# sch1.net
KiCad netlist of a schematic drawn in EAGLE
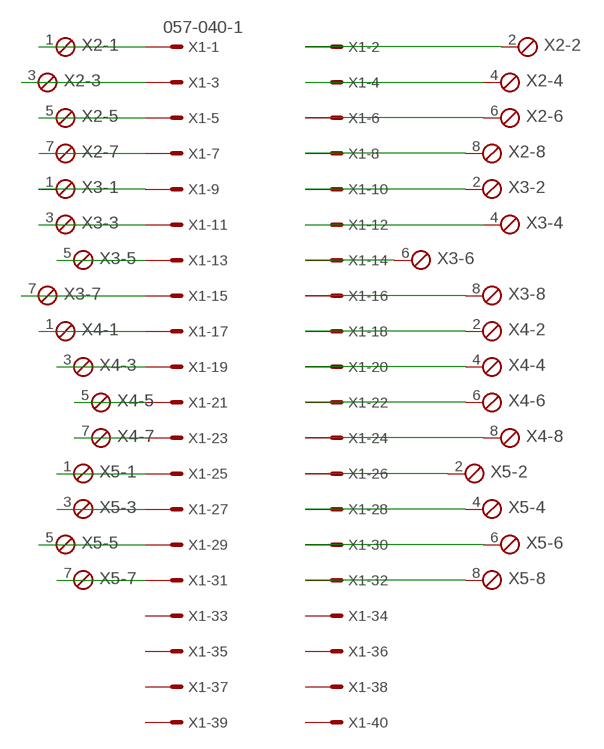
[diagram p0: schematic, sheet 1]

(export (version "E")
  (design (tool "Eeschema 10.0.6"))
  (components
    (comp (ref "X1")
      (value "057-040-1")
      (footprint "eagle-import:057-040-1")
      (libsource (lib "eagle-import") (part "057-040-1"))
    )
    (comp (ref "X2")
      (value "MPT8")
      (footprint "eagle-import:8POL254")
      (libsource (lib "eagle-import") (part "MPT8"))
    )
    (comp (ref "X3")
      (value "MPT8")
      (footprint "eagle-import:8POL254")
      (libsource (lib "eagle-import") (part "MPT8"))
    )
    (comp (ref "X4")
      (value "MPT8")
      (footprint "eagle-import:8POL254")
      (libsource (lib "eagle-import") (part "MPT8"))
    )
    (comp (ref "X5")
      (value "MPT8")
      (footprint "eagle-import:8POL254")
      (libsource (lib "eagle-import") (part "MPT8"))
    )
  )
  (nets
    (net (code "1") (name "Net-(X1A-S)") (class "Default")
      (node (ref "X1") (pin "1") (pinfunction "S_1") (pintype "passive"))
      (node (ref "X2") (pin "1") (pinfunction "1_1") (pintype "passive"))
    )
    (net (code "2") (name "Net-(X1AH-S)") (class "Default")
      (node (ref "X1") (pin "4") (pinfunction "S_4") (pintype "passive"))
      (node (ref "X2") (pin "4") (pinfunction "1_4") (pintype "passive"))
    )
    (net (code "3") (name "Net-(X1AJ-S)") (class "Default")
      (node (ref "X1") (pin "5") (pinfunction "S_5") (pintype "passive"))
      (node (ref "X2") (pin "5") (pinfunction "1_5") (pintype "passive"))
    )
    (net (code "4") (name "Net-(X1AK-S)") (class "Default")
      (node (ref "X1") (pin "6") (pinfunction "S_6") (pintype "passive"))
      (node (ref "X2") (pin "6") (pinfunction "1_6") (pintype "passive"))
    )
    (net (code "5") (name "Net-(X1AL-S)") (class "Default")
      (node (ref "X1") (pin "7") (pinfunction "S_7") (pintype "passive"))
      (node (ref "X2") (pin "7") (pinfunction "1_7") (pintype "passive"))
    )
    (net (code "6") (name "Net-(X1AM-S)") (class "Default")
      (node (ref "X1") (pin "8") (pinfunction "S_8") (pintype "passive"))
      (node (ref "X2") (pin "8") (pinfunction "1_8") (pintype "passive"))
    )
    (net (code "7") (name "Net-(X1AN-S)") (class "Default")
      (node (ref "X1") (pin "9") (pinfunction "S_9") (pintype "passive"))
      (node (ref "X3") (pin "1") (pinfunction "1_1") (pintype "passive"))
    )
    (net (code "8") (name "Net-(X1B-S)") (class "Default")
      (node (ref "X1") (pin "10") (pinfunction "S_10") (pintype "passive"))
      (node (ref "X3") (pin "2") (pinfunction "1_2") (pintype "passive"))
    )
    (net (code "9") (name "Net-(X1C-S)") (class "Default")
      (node (ref "X1") (pin "11") (pinfunction "S_11") (pintype "passive"))
      (node (ref "X3") (pin "3") (pinfunction "1_3") (pintype "passive"))
    )
    (net (code "10") (name "Net-(X1D-S)") (class "Default")
      (node (ref "X1") (pin "12") (pinfunction "S_12") (pintype "passive"))
      (node (ref "X3") (pin "4") (pinfunction "1_4") (pintype "passive"))
    )
    (net (code "11") (name "Net-(X1E-S)") (class "Default")
      (node (ref "X1") (pin "13") (pinfunction "S_13") (pintype "passive"))
      (node (ref "X3") (pin "5") (pinfunction "1_5") (pintype "passive"))
    )
    (net (code "12") (name "Net-(X1F-S)") (class "Default")
      (node (ref "X1") (pin "14") (pinfunction "S_14") (pintype "passive"))
      (node (ref "X3") (pin "6") (pinfunction "1_6") (pintype "passive"))
    )
    (net (code "13") (name "Net-(X1G-S)") (class "Default")
      (node (ref "X1") (pin "15") (pinfunction "S_15") (pintype "passive"))
      (node (ref "X3") (pin "7") (pinfunction "1_7") (pintype "passive"))
    )
    (net (code "14") (name "Net-(X1H-S)") (class "Default")
      (node (ref "X1") (pin "16") (pinfunction "S_16") (pintype "passive"))
      (node (ref "X3") (pin "8") (pinfunction "1_8") (pintype "passive"))
    )
    (net (code "15") (name "Net-(X1I-S)") (class "Default")
      (node (ref "X1") (pin "17") (pinfunction "S_17") (pintype "passive"))
      (node (ref "X4") (pin "1") (pinfunction "1_1") (pintype "passive"))
    )
    (net (code "16") (name "Net-(X1J-S)") (class "Default")
      (node (ref "X1") (pin "18") (pinfunction "S_18") (pintype "passive"))
      (node (ref "X4") (pin "2") (pinfunction "1_2") (pintype "passive"))
    )
    (net (code "17") (name "Net-(X1K-S)") (class "Default")
      (node (ref "X1") (pin "19") (pinfunction "S_19") (pintype "passive"))
      (node (ref "X4") (pin "3") (pinfunction "1_3") (pintype "passive"))
    )
    (net (code "18") (name "Net-(X1L-S)") (class "Default")
      (node (ref "X1") (pin "2") (pinfunction "S_2") (pintype "passive"))
      (node (ref "X2") (pin "2") (pinfunction "1_2") (pintype "passive"))
    )
    (net (code "19") (name "Net-(X1M-S)") (class "Default")
      (node (ref "X1") (pin "20") (pinfunction "S_20") (pintype "passive"))
      (node (ref "X4") (pin "4") (pinfunction "1_4") (pintype "passive"))
    )
    (net (code "20") (name "Net-(X1N-S)") (class "Default")
      (node (ref "X1") (pin "21") (pinfunction "S_21") (pintype "passive"))
      (node (ref "X4") (pin "5") (pinfunction "1_5") (pintype "passive"))
    )
    (net (code "21") (name "Net-(X1O-S)") (class "Default")
      (node (ref "X1") (pin "22") (pinfunction "S_22") (pintype "passive"))
      (node (ref "X4") (pin "6") (pinfunction "1_6") (pintype "passive"))
    )
    (net (code "22") (name "Net-(X1P-S)") (class "Default")
      (node (ref "X1") (pin "23") (pinfunction "S_23") (pintype "passive"))
      (node (ref "X4") (pin "7") (pinfunction "1_7") (pintype "passive"))
    )
    (net (code "23") (name "Net-(X1Q-S)") (class "Default")
      (node (ref "X1") (pin "24") (pinfunction "S_24") (pintype "passive"))
      (node (ref "X4") (pin "8") (pinfunction "1_8") (pintype "passive"))
    )
    (net (code "24") (name "Net-(X1R-S)") (class "Default")
      (node (ref "X1") (pin "25") (pinfunction "S_25") (pintype "passive"))
      (node (ref "X5") (pin "1") (pinfunction "1_1") (pintype "passive"))
    )
    (net (code "25") (name "Net-(X1S-S)") (class "Default")
      (node (ref "X1") (pin "26") (pinfunction "S_26") (pintype "passive"))
      (node (ref "X5") (pin "2") (pinfunction "1_2") (pintype "passive"))
    )
    (net (code "26") (name "Net-(X1T-S)") (class "Default")
      (node (ref "X1") (pin "27") (pinfunction "S_27") (pintype "passive"))
      (node (ref "X5") (pin "3") (pinfunction "1_3") (pintype "passive"))
    )
    (net (code "27") (name "Net-(X1U-S)") (class "Default")
      (node (ref "X1") (pin "28") (pinfunction "S_28") (pintype "passive"))
      (node (ref "X5") (pin "4") (pinfunction "1_4") (pintype "passive"))
    )
    (net (code "28") (name "Net-(X1V-S)") (class "Default")
      (node (ref "X1") (pin "29") (pinfunction "S_29") (pintype "passive"))
      (node (ref "X5") (pin "5") (pinfunction "1_5") (pintype "passive"))
    )
    (net (code "29") (name "Net-(X1W-S)") (class "Default")
      (node (ref "X1") (pin "3") (pinfunction "S_3") (pintype "passive"))
      (node (ref "X2") (pin "3") (pinfunction "1_3") (pintype "passive"))
    )
    (net (code "30") (name "Net-(X1X-S)") (class "Default")
      (node (ref "X1") (pin "30") (pinfunction "S_30") (pintype "passive"))
      (node (ref "X5") (pin "6") (pinfunction "1_6") (pintype "passive"))
    )
    (net (code "31") (name "Net-(X1Y-S)") (class "Default")
      (node (ref "X1") (pin "31") (pinfunction "S_31") (pintype "passive"))
      (node (ref "X5") (pin "7") (pinfunction "1_7") (pintype "passive"))
    )
    (net (code "32") (name "Net-(X1Z-S)") (class "Default")
      (node (ref "X1") (pin "32") (pinfunction "S_32") (pintype "passive"))
      (node (ref "X5") (pin "8") (pinfunction "1_8") (pintype "passive"))
    )
    (net (code "33") (name "unconnected-(X1AA-S-Pad33)") (class "Default")
      (node (ref "X1") (pin "33") (pinfunction "S_33") (pintype "passive"))
    )
    (net (code "34") (name "unconnected-(X1AB-S-Pad34)") (class "Default")
      (node (ref "X1") (pin "34") (pinfunction "S_34") (pintype "passive"))
    )
    (net (code "35") (name "unconnected-(X1AC-S-Pad35)") (class "Default")
      (node (ref "X1") (pin "35") (pinfunction "S_35") (pintype "passive"))
    )
    (net (code "36") (name "unconnected-(X1AD-S-Pad36)") (class "Default")
      (node (ref "X1") (pin "36") (pinfunction "S_36") (pintype "passive"))
    )
    (net (code "37") (name "unconnected-(X1AE-S-Pad37)") (class "Default")
      (node (ref "X1") (pin "37") (pinfunction "S_37") (pintype "passive"))
    )
    (net (code "38") (name "unconnected-(X1AF-S-Pad38)") (class "Default")
      (node (ref "X1") (pin "38") (pinfunction "S_38") (pintype "passive"))
    )
    (net (code "39") (name "unconnected-(X1AG-S-Pad39)") (class "Default")
      (node (ref "X1") (pin "39") (pinfunction "S_39") (pintype "passive"))
    )
    (net (code "40") (name "unconnected-(X1AI-S-Pad40)") (class "Default")
      (node (ref "X1") (pin "40") (pinfunction "S_40") (pintype "passive"))
    )
  )
)
